# Replica.net
KiCad netlist of a schematic drawn in EAGLE
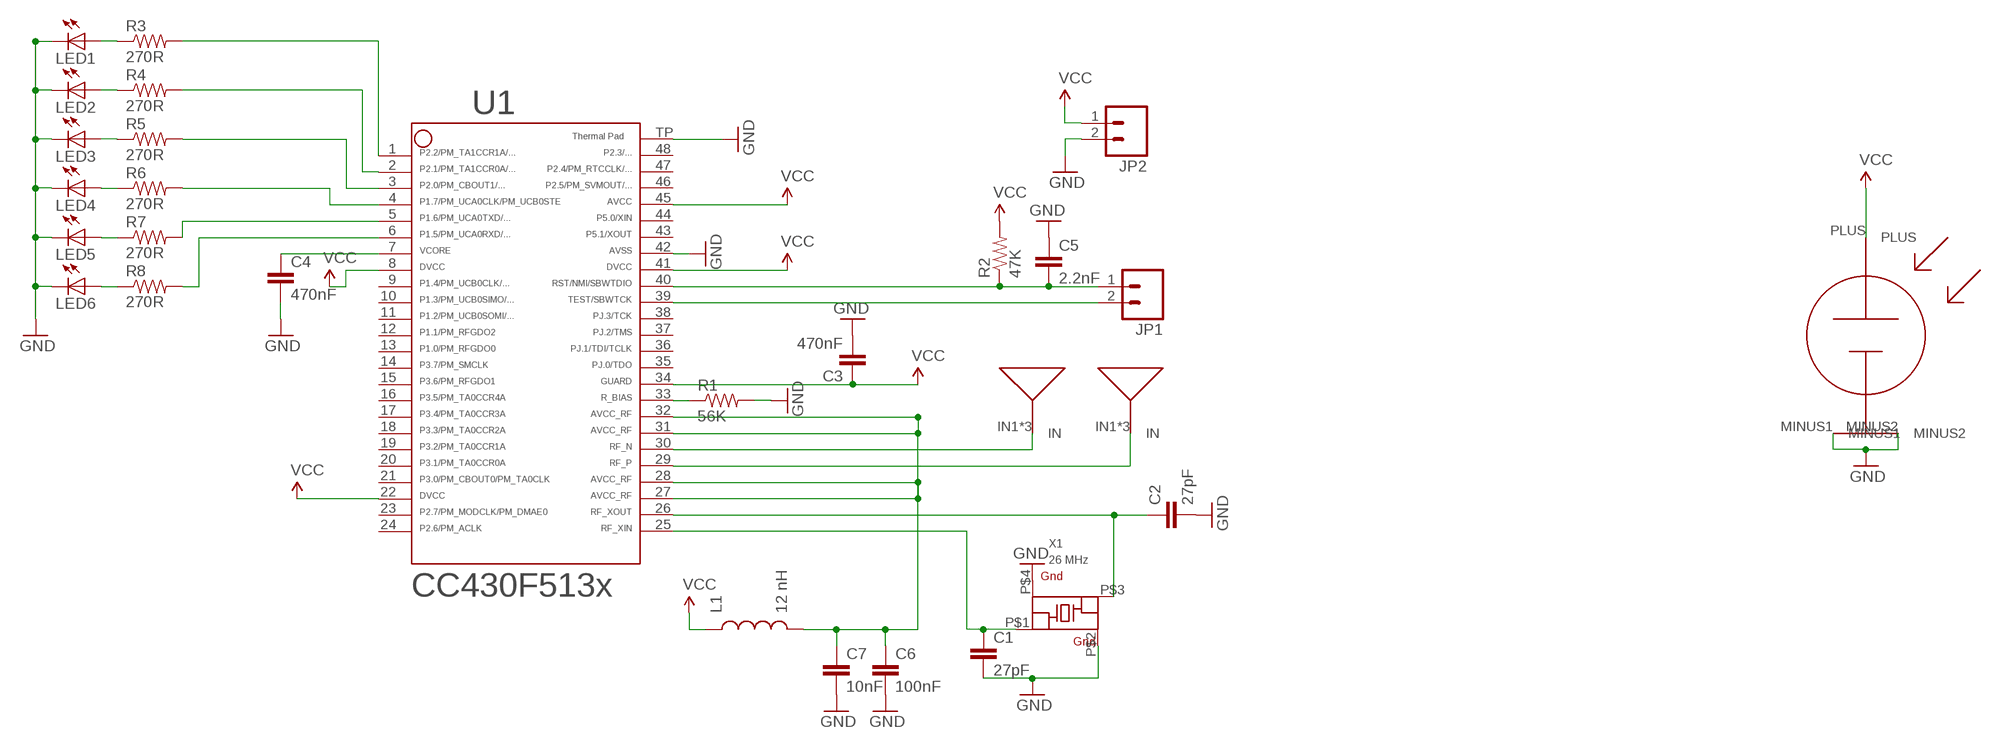
[diagram p0: schematic, sheet 1]

(export (version "E")
  (design (tool "Eeschema 10.0.6"))
  (components
    (comp (ref "ANT-N")
      (value "ANTENNA")
      (footprint "eagle-import:ANTENNA")
      (libsource (lib "eagle-import") (part "ANTENNA"))
    )
    (comp (ref "ANT-P")
      (value "ANTENNA")
      (footprint "eagle-import:ANTENNA")
      (libsource (lib "eagle-import") (part "ANTENNA"))
    )
    (comp (ref "C1")
      (value "27pF")
      (footprint "eagle-import:0603-CAP")
      (libsource (lib "eagle-import") (part "CAP0603-CAP"))
    )
    (comp (ref "C2")
      (value "27pF")
      (footprint "eagle-import:0603-CAP")
      (libsource (lib "eagle-import") (part "CAP0603-CAP"))
    )
    (comp (ref "C3")
      (value "470nF")
      (footprint "eagle-import:0603-CAP")
      (libsource (lib "eagle-import") (part "CAP0603-CAP"))
    )
    (comp (ref "C4")
      (value "470nF")
      (footprint "eagle-import:0603-CAP")
      (libsource (lib "eagle-import") (part "CAP0603-CAP"))
    )
    (comp (ref "C5")
      (value "2.2nF")
      (footprint "eagle-import:0603-CAP")
      (libsource (lib "eagle-import") (part "CAP0603-CAP"))
    )
    (comp (ref "C6")
      (value "100nF")
      (footprint "eagle-import:0603-CAP")
      (libsource (lib "eagle-import") (part "CAP0603-CAP"))
    )
    (comp (ref "C7")
      (value "10nF")
      (footprint "eagle-import:0603-CAP")
      (libsource (lib "eagle-import") (part "CAP0603-CAP"))
    )
    (comp (ref "JP1")
      (value "M02PTH")
      (footprint "eagle-import:1X02")
      (libsource (lib "eagle-import") (part "M02PTH"))
    )
    (comp (ref "JP2")
      (value "M02PTH")
      (footprint "eagle-import:1X02")
      (libsource (lib "eagle-import") (part "M02PTH"))
    )
    (comp (ref "L1")
      (value "12 nH")
      (footprint "eagle-import:0603")
      (libsource (lib "eagle-import") (part "INDUCTOR0603"))
    )
    (comp (ref "LED1")
      (value "LED0603")
      (footprint "eagle-import:LED-0603")
      (libsource (lib "eagle-import") (part "LED0603"))
    )
    (comp (ref "LED2")
      (value "LED0603")
      (footprint "eagle-import:LED-0603")
      (libsource (lib "eagle-import") (part "LED0603"))
    )
    (comp (ref "LED3")
      (value "LED0603")
      (footprint "eagle-import:LED-0603")
      (libsource (lib "eagle-import") (part "LED0603"))
    )
    (comp (ref "LED4")
      (value "LED0603")
      (footprint "eagle-import:LED-0603")
      (libsource (lib "eagle-import") (part "LED0603"))
    )
    (comp (ref "LED5")
      (value "LED0603")
      (footprint "eagle-import:LED-0603")
      (libsource (lib "eagle-import") (part "LED0603"))
    )
    (comp (ref "LED6")
      (value "LED0603")
      (footprint "eagle-import:LED-0603")
      (libsource (lib "eagle-import") (part "LED0603"))
    )
    (comp (ref "R1")
      (value "56K")
      (footprint "eagle-import:0603-RES")
      (libsource (lib "eagle-import") (part "RESISTOR0603-RES"))
    )
    (comp (ref "R2")
      (value "47K")
      (footprint "eagle-import:0603-RES")
      (libsource (lib "eagle-import") (part "RESISTOR0603-RES"))
    )
    (comp (ref "R3")
      (value "270R")
      (footprint "eagle-import:0603-RES")
      (libsource (lib "eagle-import") (part "RESISTOR0603-RES"))
    )
    (comp (ref "R4")
      (value "270R")
      (footprint "eagle-import:0603-RES")
      (libsource (lib "eagle-import") (part "RESISTOR0603-RES"))
    )
    (comp (ref "R5")
      (value "270R")
      (footprint "eagle-import:0603-RES")
      (libsource (lib "eagle-import") (part "RESISTOR0603-RES"))
    )
    (comp (ref "R6")
      (value "270R")
      (footprint "eagle-import:0603-RES")
      (libsource (lib "eagle-import") (part "RESISTOR0603-RES"))
    )
    (comp (ref "R7")
      (value "270R")
      (footprint "eagle-import:0603-RES")
      (libsource (lib "eagle-import") (part "RESISTOR0603-RES"))
    )
    (comp (ref "R8")
      (value "270R")
      (footprint "eagle-import:0603-RES")
      (libsource (lib "eagle-import") (part "RESISTOR0603-RES"))
    )
    (comp (ref "S1")
      (value "TASC")
      (footprint "eagle-import:TASC")
      (libsource (lib "eagle-import") (part "TASC"))
    )
    (comp (ref "U1")
      (value "CC430F5137")
      (footprint "eagle-import:RGZ48")
      (libsource (lib "eagle-import") (part "CC430F513X---RGZ48"))
    )
    (comp (ref "X1")
      (value "26 MHz")
      (footprint "eagle-import:ABM11_CERAMIC-SMD-CRYSTAL")
      (libsource (lib "eagle-import") (part "ABM11_CERAMIC_SMD_CRYSTALABM11"))
    )
  )
  (nets
    (net (code "1") (name "GND") (class "Default")
      (node (ref "C1") (pin "2") (pinfunction "2_2") (pintype "passive"))
      (node (ref "C2") (pin "2") (pinfunction "2_2") (pintype "passive"))
      (node (ref "C3") (pin "2") (pinfunction "2_2") (pintype "passive"))
      (node (ref "C4") (pin "2") (pinfunction "2_2") (pintype "passive"))
      (node (ref "C5") (pin "1") (pinfunction "1_1") (pintype "passive"))
      (node (ref "C6") (pin "2") (pinfunction "2_2") (pintype "passive"))
      (node (ref "C7") (pin "2") (pinfunction "2_2") (pintype "passive"))
      (node (ref "JP2") (pin "2") (pinfunction "2_2") (pintype "passive"))
      (node (ref "LED1") (pin "C") (pinfunction "C_C") (pintype "passive"))
      (node (ref "LED2") (pin "C") (pinfunction "C_C") (pintype "passive"))
      (node (ref "LED3") (pin "C") (pinfunction "C_C") (pintype "passive"))
      (node (ref "LED4") (pin "C") (pinfunction "C_C") (pintype "passive"))
      (node (ref "LED5") (pin "C") (pinfunction "C_C") (pintype "passive"))
      (node (ref "LED6") (pin "C") (pinfunction "C_C") (pintype "passive"))
      (node (ref "R1") (pin "2") (pinfunction "2_2") (pintype "passive"))
      (node (ref "S1") (pin "MINUS1") (pinfunction "MINUS1_MINUS1") (pintype "power_in"))
      (node (ref "S1") (pin "MINUS2") (pinfunction "MINUS2_MINUS2") (pintype "power_in"))
      (node (ref "U1") (pin "42") (pinfunction "42_42") (pintype "power_in"))
      (node (ref "U1") (pin "TP") (pinfunction "49_TP") (pintype "power_in"))
      (node (ref "X1") (pin "P$2") (pinfunction "GROUND2_P$2") (pintype "bidirectional"))
      (node (ref "X1") (pin "P$4") (pinfunction "GROUND4_P$4") (pintype "bidirectional"))
    )
    (net (code "2") (name "Net-(ANT-N-IN-PadIN1)") (class "Default")
      (node (ref "ANT-N") (pin "IN1") (pinfunction "IN_IN1") (pintype "bidirectional"))
      (node (ref "ANT-N") (pin "IN2") (pinfunction "IN_IN2") (pintype "bidirectional"))
      (node (ref "ANT-N") (pin "IN3") (pinfunction "IN_IN3") (pintype "bidirectional"))
      (node (ref "U1") (pin "30") (pinfunction "30_30") (pintype "bidirectional"))
    )
    (net (code "3") (name "Net-(ANT-P-IN-PadIN1)") (class "Default")
      (node (ref "ANT-P") (pin "IN1") (pinfunction "IN_IN1") (pintype "bidirectional"))
      (node (ref "ANT-P") (pin "IN2") (pinfunction "IN_IN2") (pintype "bidirectional"))
      (node (ref "ANT-P") (pin "IN3") (pinfunction "IN_IN3") (pintype "bidirectional"))
      (node (ref "U1") (pin "29") (pinfunction "29_29") (pintype "bidirectional"))
    )
    (net (code "4") (name "Net-(C1-Pad1)") (class "Default")
      (node (ref "C1") (pin "1") (pinfunction "1_1") (pintype "passive"))
      (node (ref "U1") (pin "25") (pinfunction "25_25") (pintype "input"))
      (node (ref "X1") (pin "P$1") (pinfunction "P$1_P$1") (pintype "bidirectional"))
    )
    (net (code "5") (name "Net-(C2-Pad1)") (class "Default")
      (node (ref "C2") (pin "1") (pinfunction "1_1") (pintype "passive"))
      (node (ref "U1") (pin "26") (pinfunction "26_26") (pintype "output"))
      (node (ref "X1") (pin "P$3") (pinfunction "P$3_P$3") (pintype "bidirectional"))
    )
    (net (code "6") (name "Net-(C4-Pad1)") (class "Default")
      (node (ref "C4") (pin "1") (pinfunction "1_1") (pintype "passive"))
      (node (ref "U1") (pin "7") (pinfunction "7_7") (pintype "power_in"))
    )
    (net (code "7") (name "Net-(C5-Pad2)") (class "Default")
      (node (ref "C5") (pin "2") (pinfunction "2_2") (pintype "passive"))
      (node (ref "JP1") (pin "1") (pinfunction "1_1") (pintype "passive"))
      (node (ref "R2") (pin "1") (pinfunction "1_1") (pintype "passive"))
      (node (ref "U1") (pin "40") (pinfunction "40_40") (pintype "bidirectional"))
    )
    (net (code "8") (name "Net-(C6-Pad1)") (class "Default")
      (node (ref "C6") (pin "1") (pinfunction "1_1") (pintype "passive"))
      (node (ref "C7") (pin "1") (pinfunction "1_1") (pintype "passive"))
      (node (ref "L1") (pin "2") (pinfunction "2_2") (pintype "passive"))
      (node (ref "U1") (pin "27") (pinfunction "27_27") (pintype "power_in"))
      (node (ref "U1") (pin "28") (pinfunction "28_28") (pintype "bidirectional"))
      (node (ref "U1") (pin "31") (pinfunction "31_31") (pintype "power_in"))
      (node (ref "U1") (pin "32") (pinfunction "32_32") (pintype "power_in"))
    )
    (net (code "9") (name "Net-(JP1-Pad2)") (class "Default")
      (node (ref "JP1") (pin "2") (pinfunction "2_2") (pintype "passive"))
      (node (ref "U1") (pin "39") (pinfunction "39_39") (pintype "input"))
    )
    (net (code "10") (name "Net-(LED1-PadA)") (class "Default")
      (node (ref "LED1") (pin "A") (pinfunction "A_A") (pintype "passive"))
      (node (ref "R3") (pin "1") (pinfunction "1_1") (pintype "passive"))
    )
    (net (code "11") (name "Net-(LED2-PadA)") (class "Default")
      (node (ref "LED2") (pin "A") (pinfunction "A_A") (pintype "passive"))
      (node (ref "R4") (pin "1") (pinfunction "1_1") (pintype "passive"))
    )
    (net (code "12") (name "Net-(LED3-PadA)") (class "Default")
      (node (ref "LED3") (pin "A") (pinfunction "A_A") (pintype "passive"))
      (node (ref "R5") (pin "1") (pinfunction "1_1") (pintype "passive"))
    )
    (net (code "13") (name "Net-(LED4-PadA)") (class "Default")
      (node (ref "LED4") (pin "A") (pinfunction "A_A") (pintype "passive"))
      (node (ref "R6") (pin "1") (pinfunction "1_1") (pintype "passive"))
    )
    (net (code "14") (name "Net-(LED5-PadA)") (class "Default")
      (node (ref "LED5") (pin "A") (pinfunction "A_A") (pintype "passive"))
      (node (ref "R7") (pin "1") (pinfunction "1_1") (pintype "passive"))
    )
    (net (code "15") (name "Net-(LED6-PadA)") (class "Default")
      (node (ref "LED6") (pin "A") (pinfunction "A_A") (pintype "passive"))
      (node (ref "R8") (pin "1") (pinfunction "1_1") (pintype "passive"))
    )
    (net (code "16") (name "Net-(R1-Pad1)") (class "Default")
      (node (ref "R1") (pin "1") (pinfunction "1_1") (pintype "passive"))
      (node (ref "U1") (pin "33") (pinfunction "33_33") (pintype "power_in"))
    )
    (net (code "17") (name "Net-(R3-Pad2)") (class "Default")
      (node (ref "R3") (pin "2") (pinfunction "2_2") (pintype "passive"))
      (node (ref "U1") (pin "1") (pinfunction "1_1") (pintype "bidirectional"))
    )
    (net (code "18") (name "Net-(R4-Pad2)") (class "Default")
      (node (ref "R4") (pin "2") (pinfunction "2_2") (pintype "passive"))
      (node (ref "U1") (pin "2") (pinfunction "2_2") (pintype "bidirectional"))
    )
    (net (code "19") (name "Net-(R5-Pad2)") (class "Default")
      (node (ref "R5") (pin "2") (pinfunction "2_2") (pintype "passive"))
      (node (ref "U1") (pin "3") (pinfunction "3_3") (pintype "bidirectional"))
    )
    (net (code "20") (name "Net-(R6-Pad2)") (class "Default")
      (node (ref "R6") (pin "2") (pinfunction "2_2") (pintype "passive"))
      (node (ref "U1") (pin "4") (pinfunction "4_4") (pintype "bidirectional"))
    )
    (net (code "21") (name "Net-(R7-Pad2)") (class "Default")
      (node (ref "R7") (pin "2") (pinfunction "2_2") (pintype "passive"))
      (node (ref "U1") (pin "5") (pinfunction "5_5") (pintype "bidirectional"))
    )
    (net (code "22") (name "Net-(R8-Pad2)") (class "Default")
      (node (ref "R8") (pin "2") (pinfunction "2_2") (pintype "passive"))
      (node (ref "U1") (pin "6") (pinfunction "6_6") (pintype "bidirectional"))
    )
    (net (code "23") (name "VCC") (class "Default")
      (node (ref "C3") (pin "1") (pinfunction "1_1") (pintype "passive"))
      (node (ref "JP2") (pin "1") (pinfunction "1_1") (pintype "passive"))
      (node (ref "L1") (pin "1") (pinfunction "1_1") (pintype "passive"))
      (node (ref "R2") (pin "2") (pinfunction "2_2") (pintype "passive"))
      (node (ref "S1") (pin "PLUS") (pinfunction "PLUS_PLUS") (pintype "power_in"))
      (node (ref "U1") (pin "22") (pinfunction "22_22") (pintype "power_in"))
      (node (ref "U1") (pin "34") (pinfunction "34_34") (pintype "power_in"))
      (node (ref "U1") (pin "41") (pinfunction "41_41") (pintype "power_in"))
      (node (ref "U1") (pin "45") (pinfunction "45_45") (pintype "input"))
      (node (ref "U1") (pin "8") (pinfunction "8_8") (pintype "power_in"))
    )
    (net (code "24") (name "unconnected-(U1-Pad9)") (class "Default")
      (node (ref "U1") (pin "9") (pinfunction "9_9") (pintype "bidirectional"))
    )
    (net (code "25") (name "unconnected-(U1-Pad10)") (class "Default")
      (node (ref "U1") (pin "10") (pinfunction "10_10") (pintype "bidirectional"))
    )
    (net (code "26") (name "unconnected-(U1-Pad11)") (class "Default")
      (node (ref "U1") (pin "11") (pinfunction "11_11") (pintype "bidirectional"))
    )
    (net (code "27") (name "unconnected-(U1-Pad12)") (class "Default")
      (node (ref "U1") (pin "12") (pinfunction "12_12") (pintype "bidirectional"))
    )
    (net (code "28") (name "unconnected-(U1-Pad13)") (class "Default")
      (node (ref "U1") (pin "13") (pinfunction "13_13") (pintype "bidirectional"))
    )
    (net (code "29") (name "unconnected-(U1-Pad14)") (class "Default")
      (node (ref "U1") (pin "14") (pinfunction "14_14") (pintype "bidirectional"))
    )
    (net (code "30") (name "unconnected-(U1-Pad15)") (class "Default")
      (node (ref "U1") (pin "15") (pinfunction "15_15") (pintype "bidirectional"))
    )
    (net (code "31") (name "unconnected-(U1-Pad16)") (class "Default")
      (node (ref "U1") (pin "16") (pinfunction "16_16") (pintype "bidirectional"))
    )
    (net (code "32") (name "unconnected-(U1-Pad17)") (class "Default")
      (node (ref "U1") (pin "17") (pinfunction "17_17") (pintype "bidirectional"))
    )
    (net (code "33") (name "unconnected-(U1-Pad18)") (class "Default")
      (node (ref "U1") (pin "18") (pinfunction "18_18") (pintype "bidirectional"))
    )
    (net (code "34") (name "unconnected-(U1-Pad19)") (class "Default")
      (node (ref "U1") (pin "19") (pinfunction "19_19") (pintype "bidirectional"))
    )
    (net (code "35") (name "unconnected-(U1-Pad20)") (class "Default")
      (node (ref "U1") (pin "20") (pinfunction "20_20") (pintype "bidirectional"))
    )
    (net (code "36") (name "unconnected-(U1-Pad21)") (class "Default")
      (node (ref "U1") (pin "21") (pinfunction "21_21") (pintype "bidirectional"))
    )
    (net (code "37") (name "unconnected-(U1-Pad23)") (class "Default")
      (node (ref "U1") (pin "23") (pinfunction "23_23") (pintype "bidirectional"))
    )
    (net (code "38") (name "unconnected-(U1-Pad24)") (class "Default")
      (node (ref "U1") (pin "24") (pinfunction "24_24") (pintype "bidirectional"))
    )
    (net (code "39") (name "unconnected-(U1-Pad35)") (class "Default")
      (node (ref "U1") (pin "35") (pinfunction "35_35") (pintype "bidirectional"))
    )
    (net (code "40") (name "unconnected-(U1-Pad36)") (class "Default")
      (node (ref "U1") (pin "36") (pinfunction "36_36") (pintype "bidirectional"))
    )
    (net (code "41") (name "unconnected-(U1-Pad37)") (class "Default")
      (node (ref "U1") (pin "37") (pinfunction "37_37") (pintype "bidirectional"))
    )
    (net (code "42") (name "unconnected-(U1-Pad38)") (class "Default")
      (node (ref "U1") (pin "38") (pinfunction "38_38") (pintype "bidirectional"))
    )
    (net (code "43") (name "unconnected-(U1-Pad43)") (class "Default")
      (node (ref "U1") (pin "43") (pinfunction "43_43") (pintype "input"))
    )
    (net (code "44") (name "unconnected-(U1-Pad44)") (class "Default")
      (node (ref "U1") (pin "44") (pinfunction "44_44") (pintype "input"))
    )
    (net (code "45") (name "unconnected-(U1-Pad46)") (class "Default")
      (node (ref "U1") (pin "46") (pinfunction "46_46") (pintype "bidirectional"))
    )
    (net (code "46") (name "unconnected-(U1-Pad47)") (class "Default")
      (node (ref "U1") (pin "47") (pinfunction "47_47") (pintype "input"))
    )
    (net (code "47") (name "unconnected-(U1-Pad48)") (class "Default")
      (node (ref "U1") (pin "48") (pinfunction "48_48") (pintype "bidirectional"))
    )
  )
)
